# KeyBoard-RP2040_P1.net
KiCad netlist of a schematic drawn in Altium Designer
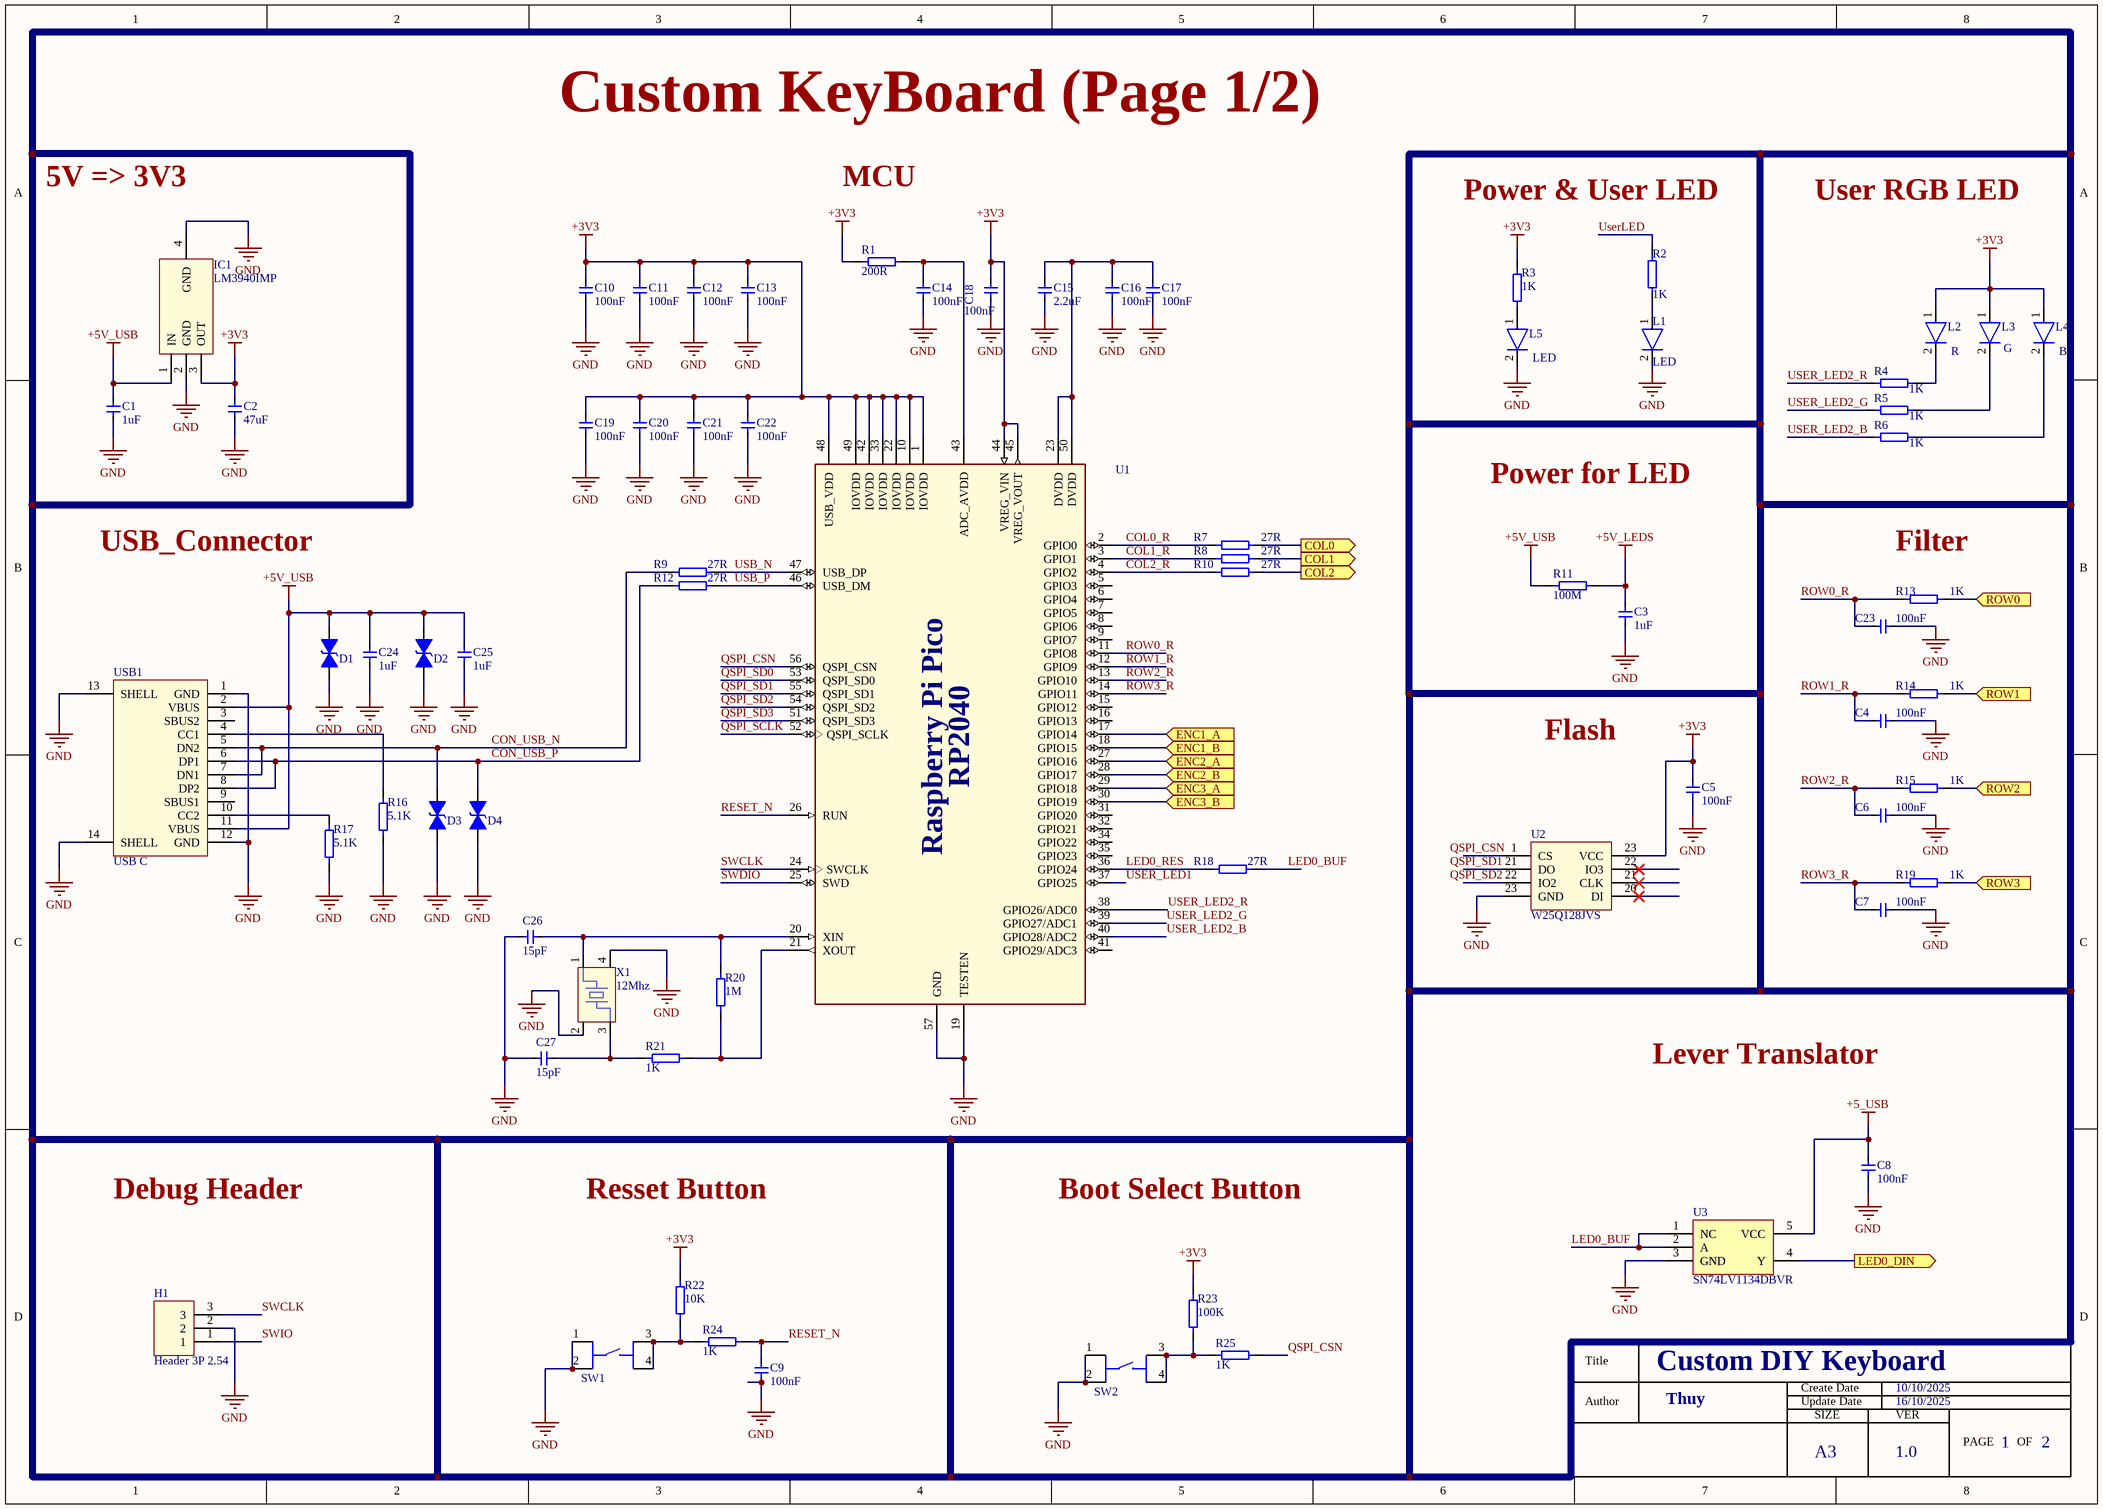
[diagram p0: KeyBoard-RP2040_P1.SchDoc]

(export (version "E")
  (design (tool "Eeschema 10.0.6"))
  (components
    (comp (ref "C1")
      (value "1uF")
      (footprint "C 0.79 0.54")
      (description "SMD 0402")
      (libsource (lib "SCHLib") (part "CAP 1uF"))
    )
    (comp (ref "C2")
      (value "47uF")
      (footprint "C 1.485 1.728")
      (description "SMD")
      (libsource (lib "SCHLib") (part "CAP 47uF"))
    )
    (comp (ref "C3")
      (value "1uF")
      (footprint "C 0.79 0.54")
      (description "SMD 0402")
      (libsource (lib "SCHLib") (part "CAP 1uF"))
    )
    (comp (ref "C4")
      (value "100nF")
      (footprint "C 0.79 0.54")
      (description "SMD")
      (libsource (lib "SCHLib") (part "CAP 100nF"))
    )
    (comp (ref "C5")
      (value "100nF")
      (footprint "C 0.79 0.54")
      (description "SMD")
      (libsource (lib "SCHLib") (part "CAP 100nF"))
    )
    (comp (ref "C6")
      (value "100nF")
      (footprint "C 0.79 0.54")
      (description "SMD")
      (libsource (lib "SCHLib") (part "CAP 100nF"))
    )
    (comp (ref "C7")
      (value "100nF")
      (footprint "C 0.79 0.54")
      (description "SMD")
      (libsource (lib "SCHLib") (part "CAP 100nF"))
    )
    (comp (ref "C8")
      (value "100nF")
      (footprint "C 0.79 0.54")
      (description "SMD")
      (libsource (lib "SCHLib") (part "CAP 100nF"))
    )
    (comp (ref "C9")
      (value "100nF")
      (footprint "C 0.79 0.54")
      (description "SMD")
      (libsource (lib "SCHLib") (part "CAP 100nF"))
    )
    (comp (ref "C10")
      (value "100nF")
      (footprint "C 0.79 0.54")
      (description "SMD")
      (libsource (lib "SCHLib") (part "CAP 100nF"))
    )
    (comp (ref "C11")
      (value "100nF")
      (footprint "C 0.79 0.54")
      (description "SMD")
      (libsource (lib "SCHLib") (part "CAP 100nF"))
    )
    (comp (ref "C12")
      (value "100nF")
      (footprint "C 0.79 0.54")
      (description "SMD")
      (libsource (lib "SCHLib") (part "CAP 100nF"))
    )
    (comp (ref "C13")
      (value "100nF")
      (footprint "C 0.79 0.54")
      (description "SMD")
      (libsource (lib "SCHLib") (part "CAP 100nF"))
    )
    (comp (ref "C14")
      (value "100nF")
      (footprint "C 0.79 0.54")
      (description "SMD")
      (libsource (lib "SCHLib") (part "CAP 100nF"))
    )
    (comp (ref "C15")
      (value "2.2uF")
      (footprint "C 0.79 0.54")
      (description "SMD")
      (libsource (lib "SCHLib") (part "CAP 2.2uF"))
    )
    (comp (ref "C16")
      (value "100nF")
      (footprint "C 0.79 0.54")
      (description "SMD")
      (libsource (lib "SCHLib") (part "CAP 100nF"))
    )
    (comp (ref "C17")
      (value "100nF")
      (footprint "C 0.79 0.54")
      (description "SMD")
      (libsource (lib "SCHLib") (part "CAP 100nF"))
    )
    (comp (ref "C18")
      (value "100nF")
      (footprint "C 0.79 0.54")
      (description "SMD")
      (libsource (lib "SCHLib") (part "CAP 100nF"))
    )
    (comp (ref "C19")
      (value "100nF")
      (footprint "C 0.79 0.54")
      (description "SMD")
      (libsource (lib "SCHLib") (part "CAP 100nF"))
    )
    (comp (ref "C20")
      (value "100nF")
      (footprint "C 0.79 0.54")
      (description "SMD")
      (libsource (lib "SCHLib") (part "CAP 100nF"))
    )
    (comp (ref "C21")
      (value "100nF")
      (footprint "C 0.79 0.54")
      (description "SMD")
      (libsource (lib "SCHLib") (part "CAP 100nF"))
    )
    (comp (ref "C22")
      (value "100nF")
      (footprint "C 0.79 0.54")
      (description "SMD")
      (libsource (lib "SCHLib") (part "CAP 100nF"))
    )
    (comp (ref "C23")
      (value "100nF")
      (footprint "C 0.79 0.54")
      (description "SMD")
      (libsource (lib "SCHLib") (part "CAP 100nF"))
    )
    (comp (ref "C24")
      (value "1uF")
      (footprint "C 0.79 0.54")
      (description "SMD 0402")
      (libsource (lib "SCHLib") (part "CAP 1uF"))
    )
    (comp (ref "C25")
      (value "1uF")
      (footprint "C 0.79 0.54")
      (description "SMD 0402")
      (libsource (lib "SCHLib") (part "CAP 1uF"))
    )
    (comp (ref "C26")
      (value "15pF")
      (footprint "C 0.79 0.54")
      (description "SMD")
      (libsource (lib "SCHLib") (part "CAP 15pF"))
    )
    (comp (ref "C27")
      (value "15pF")
      (footprint "C 0.79 0.54")
      (description "SMD")
      (libsource (lib "SCHLib") (part "CAP 15pF"))
    )
    (comp (ref "D1")
      (value "ESD GG0402052R542P")
      (footprint "D 0.6")
      (description "SMD")
      (libsource (lib "SCHLib") (part "ESD GG0402052R542P"))
    )
    (comp (ref "D2")
      (value "ESD GG0402052R542P")
      (footprint "D 0.6")
      (description "SMD")
      (libsource (lib "SCHLib") (part "ESD GG0402052R542P"))
    )
    (comp (ref "D3")
      (value "ESD GG0402052R542P")
      (footprint "D 0.6")
      (description "SMD")
      (libsource (lib "SCHLib") (part "ESD GG0402052R542P"))
    )
    (comp (ref "D4")
      (value "ESD GG0402052R542P")
      (footprint "D 0.6")
      (description "SMD")
      (libsource (lib "SCHLib") (part "ESD GG0402052R542P"))
    )
    (comp (ref "H1")
      (value "Header 3P 2.54")
      (footprint "Header 1x3")
      (description "THT")
      (libsource (lib "SCHLib") (part "Header 1x3"))
    )
    (comp (ref "IC1")
      (value "LM3940IMP")
      (footprint "LM39")
      (description "SOP ¦ 5v->3v3 ¦")
      (libsource (lib "SCHLib") (part "LM3940IMP"))
    )
    (comp (ref "L1") (value "LED") (footprint "LED") (libsource (lib "SCHLib") (part "LED2")))
    (comp (ref "L2") (value "R") (footprint "LED") (libsource (lib "SCHLib") (part "LED2")))
    (comp (ref "L3") (value "G") (footprint "LED") (libsource (lib "SCHLib") (part "LED2")))
    (comp (ref "L4") (value "B") (footprint "LED") (libsource (lib "SCHLib") (part "LED2")))
    (comp (ref "L5") (value "LED") (footprint "LED") (libsource (lib "SCHLib") (part "LED2")))
    (comp (ref "R1")
      (value "200R")
      (footprint "SMD 0.566 0.54")
      (description "SMD")
      (libsource (lib "SCHLib") (part "RES 200R"))
    )
    (comp (ref "R2")
      (value "1K")
      (footprint "SMD 0.566 0.54")
      (description "SMD")
      (libsource (lib "") (part "RES 1K_1"))
    )
    (comp (ref "R3")
      (value "1K")
      (footprint "SMD 0.566 0.54")
      (description "SMD")
      (libsource (lib "") (part "RES 1K_1"))
    )
    (comp (ref "R4")
      (value "1K")
      (footprint "SMD 0.566 0.54")
      (description "SMD")
      (libsource (lib "SCHLib") (part "RES 1K"))
    )
    (comp (ref "R5")
      (value "1K")
      (footprint "SMD 0.566 0.54")
      (description "SMD")
      (libsource (lib "SCHLib") (part "RES 1K"))
    )
    (comp (ref "R6")
      (value "1K")
      (footprint "SMD 0.566 0.54")
      (description "SMD")
      (libsource (lib "SCHLib") (part "RES 1K"))
    )
    (comp (ref "R7")
      (value "27R")
      (footprint "SMD 0.566 0.54")
      (description "SMD")
      (libsource (lib "SCHLib") (part "Res 27R"))
    )
    (comp (ref "R8")
      (value "27R")
      (footprint "SMD 0.566 0.54")
      (description "SMD")
      (libsource (lib "SCHLib") (part "Res 27R"))
    )
    (comp (ref "R9")
      (value "27R")
      (footprint "SMD 0.566 0.54")
      (description "SMD")
      (libsource (lib "SCHLib") (part "Res 27R"))
    )
    (comp (ref "R10")
      (value "27R")
      (footprint "SMD 0.566 0.54")
      (description "SMD")
      (libsource (lib "SCHLib") (part "Res 27R"))
    )
    (comp (ref "R11")
      (value "100M")
      (footprint "SMD 0.566 0.54")
      (description "SMD")
      (libsource (lib "SCHLib") (part "RES 100M"))
    )
    (comp (ref "R12")
      (value "27R")
      (footprint "SMD 0.566 0.54")
      (description "SMD")
      (libsource (lib "SCHLib") (part "Res 27R"))
    )
    (comp (ref "R13")
      (value "1K")
      (footprint "SMD 0.566 0.54")
      (description "SMD")
      (libsource (lib "") (part "RES 1K_2"))
    )
    (comp (ref "R14")
      (value "1K")
      (footprint "SMD 0.566 0.54")
      (description "SMD")
      (libsource (lib "") (part "RES 1K_2"))
    )
    (comp (ref "R15")
      (value "1K")
      (footprint "SMD 0.566 0.54")
      (description "SMD")
      (libsource (lib "") (part "RES 1K_2"))
    )
    (comp (ref "R16")
      (value "5.1K")
      (footprint "SMD 0.566 0.54")
      (description "SMD")
      (libsource (lib "SCHLib") (part "RES 5.1K"))
    )
    (comp (ref "R17")
      (value "5.1K")
      (footprint "SMD 0.566 0.54")
      (description "SMD")
      (libsource (lib "SCHLib") (part "RES 5.1K"))
    )
    (comp (ref "R18")
      (value "27R")
      (footprint "SMD 0.566 0.54")
      (description "SMD")
      (libsource (lib "SCHLib") (part "Res 27R"))
    )
    (comp (ref "R19")
      (value "1K")
      (footprint "SMD 0.566 0.54")
      (description "SMD")
      (libsource (lib "") (part "RES 1K_2"))
    )
    (comp (ref "R20")
      (value "1M")
      (footprint "SMD 0.566 0.54")
      (description "SMD")
      (libsource (lib "SCHLib") (part "RES 1M"))
    )
    (comp (ref "R21")
      (value "1K")
      (footprint "SMD 0.566 0.54")
      (description "SMD")
      (libsource (lib "") (part "RES 1K_2"))
    )
    (comp (ref "R22")
      (value "10K")
      (footprint "SMD 0.566 0.54")
      (description "SMD")
      (libsource (lib "SCHLib") (part "RES 10K"))
    )
    (comp (ref "R23")
      (value "100K")
      (footprint "SMD 0.566 0.54")
      (description "SMD")
      (libsource (lib "SCHLib") (part "RES 100K"))
    )
    (comp (ref "R24")
      (value "1K")
      (footprint "SMD 0.566 0.54")
      (description "SMD")
      (libsource (lib "") (part "RES 1K_2"))
    )
    (comp (ref "R25")
      (value "1K")
      (footprint "SMD 0.566 0.54")
      (description "SMD")
      (libsource (lib "") (part "RES 1K_2"))
    )
    (comp (ref "SW1")
      (value "BUTTON")
      (footprint "Button")
      (description "SMD")
      (libsource (lib "SCHLib") (part "BUTTON"))
    )
    (comp (ref "SW2")
      (value "BUTTON")
      (footprint "Button")
      (description "SMD")
      (libsource (lib "SCHLib") (part "BUTTON"))
    )
    (comp (ref "U1")
      (value "RP2040")
      (footprint "RP2040")
      (description "RP2040 chip for Raspberry Pi Pico - ARM® Cortex®-M0+ MCU 32-Bit")
      (libsource (lib "SCHLib") (part "Rasberry Pi Pico-RP2040"))
    )
    (comp (ref "U2")
      (value "W25Q128JVS")
      (footprint "W25Q128JVS")
      (description "SMD")
      (libsource (lib "SCHLib") (part "W25Q128JVS"))
    )
    (comp (ref "U3") (value "SN74LV1134DBVR") (libsource (lib "SCHLib") (part "SN74LV1134DBVR")))
    (comp (ref "USB1") (value "USB C") (footprint "USB-C") (libsource (lib "SCHLib") (part "USB C")))
    (comp (ref "X1")
      (value "12Mhz")
      (footprint "ABM8")
      (description "SMD")
      (libsource (lib "SCHLib") (part "Crystal ABM8-272-T3"))
    )
  )
  (nets
    (net (code "1") (name "+3V3") (class "Default")
      (node (ref "C10") (pin "2") (pinfunction "2_2") (pintype "passive"))
      (node (ref "C11") (pin "2") (pinfunction "2_2") (pintype "passive"))
      (node (ref "C12") (pin "2") (pinfunction "2_2") (pintype "passive"))
      (node (ref "C13") (pin "2") (pinfunction "2_2") (pintype "passive"))
      (node (ref "C18") (pin "2") (pinfunction "2_2") (pintype "passive"))
      (node (ref "C19") (pin "2") (pinfunction "2_2") (pintype "passive"))
      (node (ref "C2") (pin "2") (pinfunction "2_2") (pintype "passive"))
      (node (ref "C20") (pin "2") (pinfunction "2_2") (pintype "passive"))
      (node (ref "C21") (pin "2") (pinfunction "2_2") (pintype "passive"))
      (node (ref "C22") (pin "2") (pinfunction "2_2") (pintype "passive"))
      (node (ref "C5") (pin "2") (pinfunction "2_2") (pintype "passive"))
      (node (ref "IC1") (pin "3") (pinfunction "OUT_3") (pintype "passive"))
      (node (ref "L2") (pin "1") (pinfunction "1_1") (pintype "passive"))
      (node (ref "L3") (pin "1") (pinfunction "1_1") (pintype "passive"))
      (node (ref "L4") (pin "1") (pinfunction "1_1") (pintype "passive"))
      (node (ref "R1") (pin "1") (pinfunction "1_1") (pintype "passive"))
      (node (ref "R22") (pin "2") (pinfunction "2_2") (pintype "passive"))
      (node (ref "R23") (pin "2") (pinfunction "2_2") (pintype "passive"))
      (node (ref "R3") (pin "2") (pinfunction "2_2") (pintype "passive"))
      (node (ref "U1") (pin "1") (pinfunction "IOVDD_1") (pintype "power_in"))
      (node (ref "U1") (pin "10") (pinfunction "IOVDD_10") (pintype "power_in"))
      (node (ref "U1") (pin "22") (pinfunction "IOVDD_22") (pintype "power_in"))
      (node (ref "U1") (pin "33") (pinfunction "IOVDD_33") (pintype "power_in"))
      (node (ref "U1") (pin "42") (pinfunction "IOVDD_42") (pintype "power_in"))
      (node (ref "U1") (pin "44") (pinfunction "VREG_VIN_44") (pintype "input"))
      (node (ref "U1") (pin "45") (pinfunction "VREG_VOUT_45") (pintype "output"))
      (node (ref "U1") (pin "48") (pinfunction "USB_VDD_48") (pintype "power_in"))
      (node (ref "U1") (pin "49") (pinfunction "IOVDD_49") (pintype "power_in"))
      (node (ref "U2") (pin "23") (pinfunction "VCC_23") (pintype "passive"))
    )
    (net (code "2") (name "+5V_LEDS") (class "Default")
      (node (ref "C3") (pin "2") (pinfunction "2_2") (pintype "passive"))
      (node (ref "R11") (pin "2") (pinfunction "2_2") (pintype "passive"))
    )
    (net (code "3") (name "+5V_USB") (class "Default")
      (node (ref "C1") (pin "2") (pinfunction "2_2") (pintype "passive"))
      (node (ref "C24") (pin "2") (pinfunction "2_2") (pintype "passive"))
      (node (ref "C25") (pin "2") (pinfunction "2_2") (pintype "passive"))
      (node (ref "D1") (pin "2") (pinfunction "2_2") (pintype "passive"))
      (node (ref "D2") (pin "2") (pinfunction "2_2") (pintype "passive"))
      (node (ref "IC1") (pin "1") (pinfunction "IN_1") (pintype "passive"))
      (node (ref "R11") (pin "1") (pinfunction "1_1") (pintype "passive"))
      (node (ref "USB1") (pin "11") (pinfunction "VBUS_11") (pintype "passive"))
      (node (ref "USB1") (pin "2") (pinfunction "VBUS_2") (pintype "passive"))
    )
    (net (code "4") (name "+5_USB") (class "Default")
      (node (ref "C8") (pin "2") (pinfunction "2_2") (pintype "passive"))
      (node (ref "U3") (pin "5") (pinfunction "VCC_5") (pintype "passive"))
    )
    (net (code "5") (name "/COL0") (class "Default")
      (node (ref "R7") (pin "2") (pinfunction "2_2") (pintype "passive"))
    )
    (net (code "6") (name "/COL0_R") (class "Default")
      (node (ref "R7") (pin "1") (pinfunction "1_1") (pintype "passive"))
      (node (ref "U1") (pin "2") (pinfunction "GPIO0_2") (pintype "bidirectional"))
    )
    (net (code "7") (name "/COL1") (class "Default")
      (node (ref "R8") (pin "2") (pinfunction "2_2") (pintype "passive"))
    )
    (net (code "8") (name "/COL1_R") (class "Default")
      (node (ref "R8") (pin "1") (pinfunction "1_1") (pintype "passive"))
      (node (ref "U1") (pin "3") (pinfunction "GPIO1_3") (pintype "bidirectional"))
    )
    (net (code "9") (name "/COL2") (class "Default")
      (node (ref "R10") (pin "2") (pinfunction "2_2") (pintype "passive"))
    )
    (net (code "10") (name "/COL2_R") (class "Default")
      (node (ref "R10") (pin "1") (pinfunction "1_1") (pintype "passive"))
      (node (ref "U1") (pin "4") (pinfunction "GPIO2_4") (pintype "bidirectional"))
    )
    (net (code "11") (name "/CON_USB_N") (class "Default")
      (node (ref "D3") (pin "2") (pinfunction "2_2") (pintype "passive"))
      (node (ref "R9") (pin "1") (pinfunction "1_1") (pintype "passive"))
      (node (ref "USB1") (pin "5") (pinfunction "DN2_5") (pintype "passive"))
      (node (ref "USB1") (pin "7") (pinfunction "DN1_7") (pintype "passive"))
    )
    (net (code "12") (name "/CON_USB_P") (class "Default")
      (node (ref "D4") (pin "2") (pinfunction "2_2") (pintype "passive"))
      (node (ref "R12") (pin "1") (pinfunction "1_1") (pintype "passive"))
      (node (ref "USB1") (pin "6") (pinfunction "DP1_6") (pintype "passive"))
      (node (ref "USB1") (pin "8") (pinfunction "DP2_8") (pintype "passive"))
    )
    (net (code "13") (name "/ENC1_A") (class "Default")
      (node (ref "U1") (pin "17") (pinfunction "GPIO14_17") (pintype "bidirectional"))
    )
    (net (code "14") (name "/ENC1_B") (class "Default")
      (node (ref "U1") (pin "18") (pinfunction "GPIO15_18") (pintype "bidirectional"))
    )
    (net (code "15") (name "/ENC2_A") (class "Default")
      (node (ref "U1") (pin "27") (pinfunction "GPIO16_27") (pintype "bidirectional"))
    )
    (net (code "16") (name "/ENC2_B") (class "Default")
      (node (ref "U1") (pin "28") (pinfunction "GPIO17_28") (pintype "bidirectional"))
    )
    (net (code "17") (name "/ENC3_A") (class "Default")
      (node (ref "U1") (pin "29") (pinfunction "GPIO18_29") (pintype "bidirectional"))
    )
    (net (code "18") (name "/ENC3_B") (class "Default")
      (node (ref "U1") (pin "30") (pinfunction "GPIO19_30") (pintype "bidirectional"))
    )
    (net (code "19") (name "/LED0_BUF") (class "Default")
      (node (ref "R18") (pin "2") (pinfunction "2_2") (pintype "passive"))
      (node (ref "U3") (pin "1") (pinfunction "NC_1") (pintype "passive"))
      (node (ref "U3") (pin "2") (pinfunction "A_2") (pintype "passive"))
    )
    (net (code "20") (name "/LED0_DIN") (class "Default")
      (node (ref "U3") (pin "4") (pinfunction "Y_4") (pintype "passive"))
    )
    (net (code "21") (name "/LED0_RES") (class "Default")
      (node (ref "R18") (pin "1") (pinfunction "1_1") (pintype "passive"))
      (node (ref "U1") (pin "36") (pinfunction "GPIO24_36") (pintype "bidirectional"))
    )
    (net (code "22") (name "/QSPI_CSN") (class "Default")
      (node (ref "R25") (pin "2") (pinfunction "2_2") (pintype "passive"))
      (node (ref "U1") (pin "56") (pinfunction "QSPI_CSN_56") (pintype "bidirectional"))
    )
    (net (code "23") (name "/QSPI_SCLK") (class "Default")
      (node (ref "U1") (pin "52") (pinfunction "QSPI_SCLK_52") (pintype "bidirectional"))
    )
    (net (code "24") (name "/QSPI_SD0") (class "Default")
      (node (ref "U1") (pin "53") (pinfunction "QSPI_SD0_53") (pintype "bidirectional"))
    )
    (net (code "25") (name "/QSPI_SD1") (class "Default")
      (node (ref "U1") (pin "55") (pinfunction "QSPI_SD1_55") (pintype "bidirectional"))
    )
    (net (code "26") (name "/QSPI_SD2") (class "Default")
      (node (ref "U1") (pin "54") (pinfunction "QSPI_SD2_54") (pintype "bidirectional"))
    )
    (net (code "27") (name "/QSPI_SD3") (class "Default")
      (node (ref "U1") (pin "51") (pinfunction "QSPI_SD3_51") (pintype "bidirectional"))
    )
    (net (code "28") (name "/RESET_N") (class "Default")
      (node (ref "C9") (pin "2") (pinfunction "2_2") (pintype "passive"))
      (node (ref "R24") (pin "2") (pinfunction "2_2") (pintype "passive"))
      (node (ref "U1") (pin "26") (pinfunction "RUN_26") (pintype "input"))
    )
    (net (code "29") (name "/ROW0") (class "Default")
      (node (ref "R13") (pin "2") (pinfunction "2_2") (pintype "passive"))
    )
    (net (code "30") (name "/ROW0_R") (class "Default")
      (node (ref "C23") (pin "2") (pinfunction "2_2") (pintype "passive"))
      (node (ref "R13") (pin "1") (pinfunction "1_1") (pintype "passive"))
      (node (ref "U1") (pin "11") (pinfunction "GPIO8_11") (pintype "bidirectional"))
    )
    (net (code "31") (name "/ROW1") (class "Default")
      (node (ref "R14") (pin "2") (pinfunction "2_2") (pintype "passive"))
    )
    (net (code "32") (name "/ROW1_R") (class "Default")
      (node (ref "C4") (pin "2") (pinfunction "2_2") (pintype "passive"))
      (node (ref "R14") (pin "1") (pinfunction "1_1") (pintype "passive"))
      (node (ref "U1") (pin "12") (pinfunction "GPIO9_12") (pintype "bidirectional"))
    )
    (net (code "33") (name "/ROW2") (class "Default")
      (node (ref "R15") (pin "2") (pinfunction "2_2") (pintype "passive"))
    )
    (net (code "34") (name "/ROW2_R") (class "Default")
      (node (ref "C6") (pin "2") (pinfunction "2_2") (pintype "passive"))
      (node (ref "R15") (pin "1") (pinfunction "1_1") (pintype "passive"))
      (node (ref "U1") (pin "13") (pinfunction "GPIO10_13") (pintype "bidirectional"))
    )
    (net (code "35") (name "/ROW3") (class "Default")
      (node (ref "R19") (pin "2") (pinfunction "2_2") (pintype "passive"))
    )
    (net (code "36") (name "/ROW3_R") (class "Default")
      (node (ref "C7") (pin "2") (pinfunction "2_2") (pintype "passive"))
      (node (ref "R19") (pin "1") (pinfunction "1_1") (pintype "passive"))
      (node (ref "U1") (pin "14") (pinfunction "GPIO11_14") (pintype "bidirectional"))
    )
    (net (code "37") (name "/SWCLK") (class "Default")
      (node (ref "H1") (pin "3") (pinfunction "3_3") (pintype "passive"))
      (node (ref "U1") (pin "24") (pinfunction "SWCLK_24") (pintype "input"))
    )
    (net (code "38") (name "/SWDIO") (class "Default")
      (node (ref "U1") (pin "25") (pinfunction "SWD_25") (pintype "bidirectional"))
    )
    (net (code "39") (name "/SWIO") (class "Default")
      (node (ref "H1") (pin "1") (pinfunction "1_1") (pintype "passive"))
    )
    (net (code "40") (name "/USB_N") (class "Default")
      (node (ref "R9") (pin "2") (pinfunction "2_2") (pintype "passive"))
      (node (ref "U1") (pin "47") (pinfunction "USB_DP_47") (pintype "bidirectional"))
    )
    (net (code "41") (name "/USB_P") (class "Default")
      (node (ref "R12") (pin "2") (pinfunction "2_2") (pintype "passive"))
      (node (ref "U1") (pin "46") (pinfunction "USB_DM_46") (pintype "bidirectional"))
    )
    (net (code "42") (name "/USER_LED1") (class "Default")
      (node (ref "U1") (pin "37") (pinfunction "GPIO25_37") (pintype "bidirectional"))
    )
    (net (code "43") (name "/USER_LED2_B") (class "Default")
      (node (ref "R6") (pin "2") (pinfunction "2_2") (pintype "passive"))
      (node (ref "U1") (pin "40") (pinfunction "GPIO28/ADC2_40") (pintype "bidirectional"))
    )
    (net (code "44") (name "/USER_LED2_G") (class "Default")
      (node (ref "R5") (pin "2") (pinfunction "2_2") (pintype "passive"))
      (node (ref "U1") (pin "39") (pinfunction "GPIO27/ADC1_39") (pintype "bidirectional"))
    )
    (net (code "45") (name "/USER_LED2_R") (class "Default")
      (node (ref "R4") (pin "2") (pinfunction "2_2") (pintype "passive"))
      (node (ref "U1") (pin "38") (pinfunction "GPIO26/ADC0_38") (pintype "bidirectional"))
    )
    (net (code "46") (name "/UserLED") (class "Default")
      (node (ref "R2") (pin "2") (pinfunction "2_2") (pintype "passive"))
    )
    (net (code "47") (name "GND") (class "Default")
      (node (ref "C1") (pin "1") (pinfunction "1_1") (pintype "passive"))
      (node (ref "C10") (pin "1") (pinfunction "1_1") (pintype "passive"))
      (node (ref "C11") (pin "1") (pinfunction "1_1") (pintype "passive"))
      (node (ref "C12") (pin "1") (pinfunction "1_1") (pintype "passive"))
      (node (ref "C13") (pin "1") (pinfunction "1_1") (pintype "passive"))
      (node (ref "C14") (pin "1") (pinfunction "1_1") (pintype "passive"))
      (node (ref "C15") (pin "1") (pinfunction "1_1") (pintype "passive"))
      (node (ref "C16") (pin "1") (pinfunction "1_1") (pintype "passive"))
      (node (ref "C17") (pin "1") (pinfunction "1_1") (pintype "passive"))
      (node (ref "C18") (pin "1") (pinfunction "1_1") (pintype "passive"))
      (node (ref "C19") (pin "1") (pinfunction "1_1") (pintype "passive"))
      (node (ref "C2") (pin "1") (pinfunction "1_1") (pintype "passive"))
      (node (ref "C20") (pin "1") (pinfunction "1_1") (pintype "passive"))
      (node (ref "C21") (pin "1") (pinfunction "1_1") (pintype "passive"))
      (node (ref "C22") (pin "1") (pinfunction "1_1") (pintype "passive"))
      (node (ref "C23") (pin "1") (pinfunction "1_1") (pintype "passive"))
      (node (ref "C24") (pin "1") (pinfunction "1_1") (pintype "passive"))
      (node (ref "C25") (pin "1") (pinfunction "1_1") (pintype "passive"))
      (node (ref "C26") (pin "1") (pinfunction "1_1") (pintype "passive"))
      (node (ref "C27") (pin "1") (pinfunction "1_1") (pintype "passive"))
      (node (ref "C3") (pin "1") (pinfunction "1_1") (pintype "passive"))
      (node (ref "C4") (pin "1") (pinfunction "1_1") (pintype "passive"))
      (node (ref "C5") (pin "1") (pinfunction "1_1") (pintype "passive"))
      (node (ref "C6") (pin "1") (pinfunction "1_1") (pintype "passive"))
      (node (ref "C7") (pin "1") (pinfunction "1_1") (pintype "passive"))
      (node (ref "C8") (pin "1") (pinfunction "1_1") (pintype "passive"))
      (node (ref "C9") (pin "1") (pinfunction "1_1") (pintype "passive"))
      (node (ref "D1") (pin "1") (pinfunction "1_1") (pintype "passive"))
      (node (ref "D2") (pin "1") (pinfunction "1_1") (pintype "passive"))
      (node (ref "D3") (pin "1") (pinfunction "1_1") (pintype "passive"))
      (node (ref "D4") (pin "1") (pinfunction "1_1") (pintype "passive"))
      (node (ref "H1") (pin "2") (pinfunction "2_2") (pintype "passive"))
      (node (ref "IC1") (pin "2") (pinfunction "GND_2") (pintype "passive"))
      (node (ref "IC1") (pin "4") (pinfunction "GND_4") (pintype "passive"))
      (node (ref "L1") (pin "2") (pinfunction "2_2") (pintype "passive"))
      (node (ref "L5") (pin "2") (pinfunction "2_2") (pintype "passive"))
      (node (ref "R16") (pin "1") (pinfunction "1_1") (pintype "passive"))
      (node (ref "R17") (pin "1") (pinfunction "1_1") (pintype "passive"))
      (node (ref "SW1") (pin "1") (pinfunction "1_1") (pintype "passive"))
      (node (ref "SW1") (pin "2") (pinfunction "2_2") (pintype "passive"))
      (node (ref "SW2") (pin "1") (pinfunction "1_1") (pintype "passive"))
      (node (ref "SW2") (pin "2") (pinfunction "2_2") (pintype "passive"))
      (node (ref "U1") (pin "19") (pinfunction "TESTEN_19") (pintype "passive"))
      (node (ref "U1") (pin "57") (pinfunction "GND_57") (pintype "power_in"))
      (node (ref "U2") (pin "23") (pinfunction "GND_23") (pintype "passive"))
      (node (ref "U3") (pin "3") (pinfunction "GND_3") (pintype "passive"))
      (node (ref "USB1") (pin "1") (pinfunction "GND_1") (pintype "passive"))
      (node (ref "USB1") (pin "12") (pinfunction "GND_12") (pintype "passive"))
      (node (ref "USB1") (pin "13") (pinfunction "SHELL_13") (pintype "passive"))
      (node (ref "USB1") (pin "14") (pinfunction "SHELL_14") (pintype "passive"))
      (node (ref "X1") (pin "2") (pinfunction "GND_2") (pintype "passive"))
      (node (ref "X1") (pin "4") (pinfunction "GND_4") (pintype "passive"))
    )
    (net (code "48") (name "Net-(C15-Pad2)") (class "Default")
      (node (ref "C15") (pin "2") (pinfunction "2_2") (pintype "passive"))
      (node (ref "C16") (pin "2") (pinfunction "2_2") (pintype "passive"))
      (node (ref "C17") (pin "2") (pinfunction "2_2") (pintype "passive"))
      (node (ref "U1") (pin "23") (pinfunction "DVDD_23") (pintype "power_in"))
      (node (ref "U1") (pin "50") (pinfunction "DVDD_50") (pintype "power_in"))
    )
    (net (code "49") (name "Net-(C27-Pad2)") (class "Default")
      (node (ref "C27") (pin "2") (pinfunction "2_2") (pintype "passive"))
      (node (ref "R21") (pin "1") (pinfunction "1_1") (pintype "passive"))
      (node (ref "X1") (pin "3") (pinfunction "3_3") (pintype "passive"))
    )
    (net (code "50") (name "Net-(L1-Pad1)") (class "Default")
      (node (ref "L1") (pin "1") (pinfunction "1_1") (pintype "passive"))
      (node (ref "R2") (pin "1") (pinfunction "1_1") (pintype "passive"))
    )
    (net (code "51") (name "Net-(L2-Pad2)") (class "Default")
      (node (ref "L2") (pin "2") (pinfunction "2_2") (pintype "passive"))
      (node (ref "R4") (pin "1") (pinfunction "1_1") (pintype "passive"))
    )
    (net (code "52") (name "Net-(L3-Pad2)") (class "Default")
      (node (ref "L3") (pin "2") (pinfunction "2_2") (pintype "passive"))
      (node (ref "R5") (pin "1") (pinfunction "1_1") (pintype "passive"))
    )
    (net (code "53") (name "Net-(L4-Pad2)") (class "Default")
      (node (ref "L4") (pin "2") (pinfunction "2_2") (pintype "passive"))
      (node (ref "R6") (pin "1") (pinfunction "1_1") (pintype "passive"))
    )
    (net (code "54") (name "Net-(L5-Pad1)") (class "Default")
      (node (ref "L5") (pin "1") (pinfunction "1_1") (pintype "passive"))
      (node (ref "R3") (pin "1") (pinfunction "1_1") (pintype "passive"))
    )
    (net (code "55") (name "Net-(R22-Pad1)") (class "Default")
      (node (ref "R22") (pin "1") (pinfunction "1_1") (pintype "passive"))
      (node (ref "R24") (pin "1") (pinfunction "1_1") (pintype "passive"))
      (node (ref "SW1") (pin "3") (pinfunction "3_3") (pintype "passive"))
      (node (ref "SW1") (pin "4") (pinfunction "4_4") (pintype "passive"))
    )
    (net (code "56") (name "Net-(R23-Pad1)") (class "Default")
      (node (ref "R23") (pin "1") (pinfunction "1_1") (pintype "passive"))
      (node (ref "R25") (pin "1") (pinfunction "1_1") (pintype "passive"))
      (node (ref "SW2") (pin "3") (pinfunction "3_3") (pintype "passive"))
      (node (ref "SW2") (pin "4") (pinfunction "4_4") (pintype "passive"))
    )
    (net (code "57") (name "Net-(U1-ADC_AVDD)") (class "Default")
      (node (ref "C14") (pin "2") (pinfunction "2_2") (pintype "passive"))
      (node (ref "R1") (pin "2") (pinfunction "2_2") (pintype "passive"))
      (node (ref "U1") (pin "43") (pinfunction "ADC_AVDD_43") (pintype "power_in"))
    )
    (net (code "58") (name "Net-(U1-XIN)") (class "Default")
      (node (ref "C26") (pin "2") (pinfunction "2_2") (pintype "passive"))
      (node (ref "R20") (pin "2") (pinfunction "2_2") (pintype "passive"))
      (node (ref "U1") (pin "20") (pinfunction "XIN_20") (pintype "input"))
      (node (ref "X1") (pin "1") (pinfunction "1_1") (pintype "passive"))
    )
    (net (code "59") (name "Net-(U1-XOUT)") (class "Default")
      (node (ref "R20") (pin "1") (pinfunction "1_1") (pintype "passive"))
      (node (ref "R21") (pin "2") (pinfunction "2_2") (pintype "passive"))
      (node (ref "U1") (pin "21") (pinfunction "XOUT_21") (pintype "output"))
    )
    (net (code "60") (name "Net-(USB1-CC1)") (class "Default")
      (node (ref "R16") (pin "2") (pinfunction "2_2") (pintype "passive"))
      (node (ref "USB1") (pin "4") (pinfunction "CC1_4") (pintype "passive"))
    )
    (net (code "61") (name "Net-(USB1-CC2)") (class "Default")
      (node (ref "R17") (pin "2") (pinfunction "2_2") (pintype "passive"))
      (node (ref "USB1") (pin "10") (pinfunction "CC2_10") (pintype "passive"))
    )
    (net (code "62") (name "unconnected-(U1-GPIO3-Pad5)") (class "Default")
      (node (ref "U1") (pin "5") (pinfunction "GPIO3_5") (pintype "bidirectional"))
    )
    (net (code "63") (name "unconnected-(U1-GPIO4-Pad6)") (class "Default")
      (node (ref "U1") (pin "6") (pinfunction "GPIO4_6") (pintype "bidirectional"))
    )
    (net (code "64") (name "unconnected-(U1-GPIO5-Pad7)") (class "Default")
      (node (ref "U1") (pin "7") (pinfunction "GPIO5_7") (pintype "bidirectional"))
    )
    (net (code "65") (name "unconnected-(U1-GPIO6-Pad8)") (class "Default")
      (node (ref "U1") (pin "8") (pinfunction "GPIO6_8") (pintype "bidirectional"))
    )
    (net (code "66") (name "unconnected-(U1-GPIO7-Pad9)") (class "Default")
      (node (ref "U1") (pin "9") (pinfunction "GPIO7_9") (pintype "bidirectional"))
    )
    (net (code "67") (name "unconnected-(U1-GPIO12-Pad15)") (class "Default")
      (node (ref "U1") (pin "15") (pinfunction "GPIO12_15") (pintype "bidirectional"))
    )
    (net (code "68") (name "unconnected-(U1-GPIO13-Pad16)") (class "Default")
      (node (ref "U1") (pin "16") (pinfunction "GPIO13_16") (pintype "bidirectional"))
    )
    (net (code "69") (name "unconnected-(U1-GPIO20-Pad31)") (class "Default")
      (node (ref "U1") (pin "31") (pinfunction "GPIO20_31") (pintype "bidirectional"))
    )
    (net (code "70") (name "unconnected-(U1-GPIO21-Pad32)") (class "Default")
      (node (ref "U1") (pin "32") (pinfunction "GPIO21_32") (pintype "bidirectional"))
    )
    (net (code "71") (name "unconnected-(U1-GPIO22-Pad34)") (class "Default")
      (node (ref "U1") (pin "34") (pinfunction "GPIO22_34") (pintype "bidirectional"))
    )
    (net (code "72") (name "unconnected-(U1-GPIO23-Pad35)") (class "Default")
      (node (ref "U1") (pin "35") (pinfunction "GPIO23_35") (pintype "bidirectional"))
    )
    (net (code "73") (name "unconnected-(U1-GPIO29{slash}ADC3-Pad41)") (class "Default")
      (node (ref "U1") (pin "41") (pinfunction "GPIO29/ADC3_41") (pintype "bidirectional"))
    )
    (net (code "74") (name "unconnected-(U2-CLK-Pad21)") (class "Default")
      (node (ref "U2") (pin "21") (pinfunction "CLK_21") (pintype "passive+no_connect"))
    )
    (net (code "75") (name "unconnected-(U2-CS-Pad1)") (class "Default")
      (node (ref "U2") (pin "1") (pinfunction "CS_1") (pintype "passive"))
    )
    (net (code "76") (name "unconnected-(U2-DI-Pad20)") (class "Default")
      (node (ref "U2") (pin "20") (pinfunction "DI_20") (pintype "passive+no_connect"))
    )
    (net (code "77") (name "unconnected-(U2-DO-Pad21)") (class "Default")
      (node (ref "U2") (pin "21") (pinfunction "DO_21") (pintype "passive"))
    )
    (net (code "78") (name "unconnected-(U2-IO2-Pad22)") (class "Default")
      (node (ref "U2") (pin "22") (pinfunction "IO2_22") (pintype "passive"))
    )
    (net (code "79") (name "unconnected-(U2-IO3-Pad22)") (class "Default")
      (node (ref "U2") (pin "22") (pinfunction "IO3_22") (pintype "passive+no_connect"))
    )
    (net (code "80") (name "unconnected-(USB1-SBUS1-Pad9)") (class "Default")
      (node (ref "USB1") (pin "9") (pinfunction "SBUS1_9") (pintype "passive"))
    )
    (net (code "81") (name "unconnected-(USB1-SBUS2-Pad3)") (class "Default")
      (node (ref "USB1") (pin "3") (pinfunction "SBUS2_3") (pintype "passive"))
    )
  )
)
